# 14_TPU.net
KiCad netlist of a schematic drawn in Altium Designer
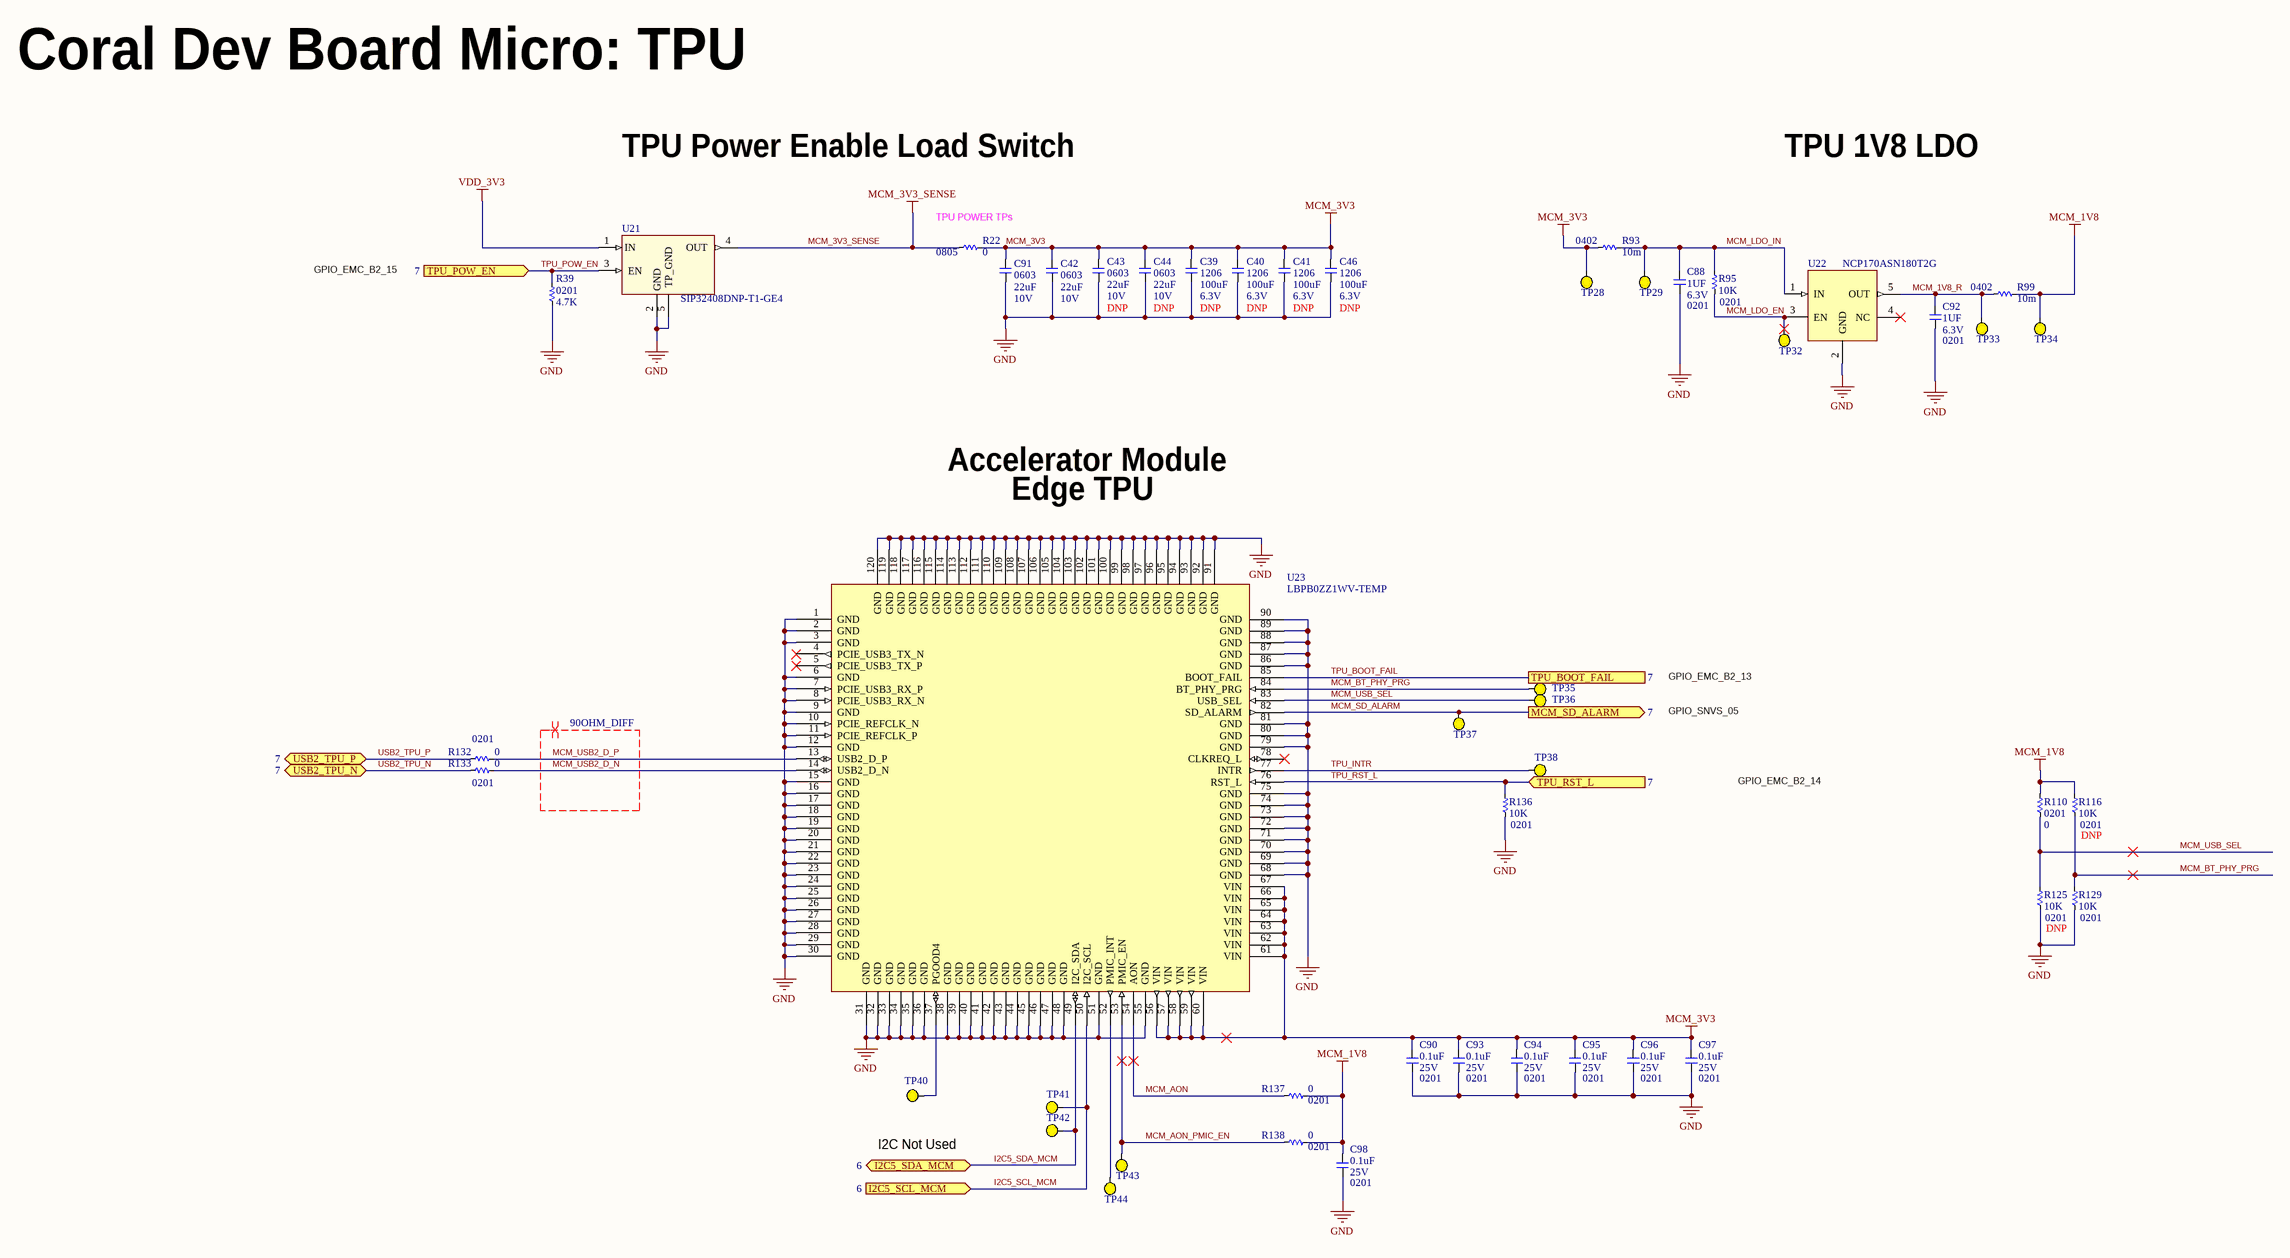
[diagram p0: 14 TPU.SchDoc]

(export (version "E")
  (design (tool "Eeschema 10.0.6"))
  (components
    (comp (ref "C39")
      (value "100uF")
      (footprint "C1206Y_1.90MM")
      (description "CAP, CER, X5R, 100UF, 6.3V, 20%, 1206")
      (fields
        (field (name "MFG") "MURATA")
        (field (name "PACKAGE") "1206")
        (field (name "VOLTAGE") "6.3V")
        (field (name "TOLERANCE") "20%")
        (field (name "DNP") "DNP")
      )
      (libsource (lib "AltiumReleaseLibDB") (part "__Template_Cap"))
    )
    (comp (ref "C40")
      (value "100uF")
      (footprint "C1206Y_1.90MM")
      (description "CAP, CER, X5R, 100UF, 6.3V, 20%, 1206")
      (fields
        (field (name "MFG") "MURATA")
        (field (name "PACKAGE") "1206")
        (field (name "VOLTAGE") "6.3V")
        (field (name "TOLERANCE") "20%")
        (field (name "DNP") "DNP")
      )
      (libsource (lib "AltiumReleaseLibDB") (part "__Template_Cap"))
    )
    (comp (ref "C41")
      (value "100uF")
      (footprint "C1206Y_1.90MM")
      (description "CAP, CER, X5R, 100UF, 6.3V, 20%, 1206")
      (fields
        (field (name "MFG") "MURATA")
        (field (name "PACKAGE") "1206")
        (field (name "VOLTAGE") "6.3V")
        (field (name "TOLERANCE") "20%")
        (field (name "DNP") "DNP")
      )
      (libsource (lib "AltiumReleaseLibDB") (part "__Template_Cap"))
    )
    (comp (ref "C42")
      (value "22uF")
      (footprint "C0603")
      (description "CAP, CER, X5R, 22uF, 20%, 10V, 0603")
      (fields
        (field (name "MFG") "TDK")
        (field (name "PACKAGE") "0603")
        (field (name "VOLTAGE") "10V")
        (field (name "TOLERANCE") "20%")
      )
      (libsource (lib "AltiumReleaseLibDB") (part "__Template_Cap"))
    )
    (comp (ref "C43")
      (value "22uF")
      (footprint "C0603")
      (description "CAP, CER, X5R, 22uF, 20%, 10V, 0603")
      (fields
        (field (name "MFG") "SAMSUNG")
        (field (name "PACKAGE") "0603")
        (field (name "VOLTAGE") "10V")
        (field (name "TOLERANCE") "20%")
        (field (name "DNP") "DNP")
      )
      (libsource (lib "AltiumReleaseLibDB") (part "__Template_Cap"))
    )
    (comp (ref "C44")
      (value "22uF")
      (footprint "C0603")
      (description "CAP, CER, X5R, 22uF, 20%, 10V, 0603")
      (fields
        (field (name "MFG") "SAMSUNG")
        (field (name "PACKAGE") "0603")
        (field (name "VOLTAGE") "10V")
        (field (name "TOLERANCE") "20%")
        (field (name "DNP") "DNP")
      )
      (libsource (lib "AltiumReleaseLibDB") (part "__Template_Cap"))
    )
    (comp (ref "C46")
      (value "100uF")
      (footprint "C1206Y_1.90MM")
      (description "CAP, CER, X5R, 100UF, 6.3V, 20%, 1206")
      (fields
        (field (name "MFG") "MURATA")
        (field (name "PACKAGE") "1206")
        (field (name "VOLTAGE") "6.3V")
        (field (name "TOLERANCE") "20%")
        (field (name "DNP") "DNP")
      )
      (libsource (lib "AltiumReleaseLibDB") (part "__Template_Cap"))
    )
    (comp (ref "C88")
      (value "1UF")
      (footprint "C0201_H0.39MM")
      (description "CAP, CER, X6S, 1uF, 20%, 6.3V, 0201, 0.39mm")
      (fields
        (field (name "MFG") "MURATA")
        (field (name "PACKAGE") "0201")
        (field (name "VOLTAGE") "6.3V")
        (field (name "TOLERANCE") "20%")
      )
      (libsource (lib "AltiumReleaseLibDB") (part "__Template_Cap"))
    )
    (comp (ref "C90")
      (value "0.1uF")
      (footprint "C0201Y")
      (description "CAP, CER, X5R, 0.1uF, 25V, 20%, 0201, 0.33mm T")
      (fields
        (field (name "MFG") "MURATA")
        (field (name "PACKAGE") "0201")
        (field (name "VOLTAGE") "25V")
        (field (name "TOLERANCE") "20%")
      )
      (libsource (lib "AltiumReleaseLibDB") (part "__Template_Cap"))
    )
    (comp (ref "C91")
      (value "22uF")
      (footprint "C0603")
      (description "CAP, CER, X5R, 22uF, 20%, 10V, 0603")
      (fields
        (field (name "MFG") "TDK")
        (field (name "PACKAGE") "0603")
        (field (name "VOLTAGE") "10V")
        (field (name "TOLERANCE") "20%")
      )
      (libsource (lib "AltiumReleaseLibDB") (part "__Template_Cap"))
    )
    (comp (ref "C92")
      (value "1UF")
      (footprint "C0201_H0.39MM")
      (description "CAP, CER, X6S, 1uF, 20%, 6.3V, 0201, 0.39mm")
      (fields
        (field (name "MFG") "MURATA")
        (field (name "PACKAGE") "0201")
        (field (name "VOLTAGE") "6.3V")
        (field (name "TOLERANCE") "20%")
      )
      (libsource (lib "AltiumReleaseLibDB") (part "__Template_Cap"))
    )
    (comp (ref "C93")
      (value "0.1uF")
      (footprint "C0201Y")
      (description "CAP, CER, X5R, 0.1uF, 25V, 20%, 0201, 0.33mm T")
      (fields
        (field (name "MFG") "MURATA")
        (field (name "PACKAGE") "0201")
        (field (name "VOLTAGE") "25V")
        (field (name "TOLERANCE") "20%")
      )
      (libsource (lib "AltiumReleaseLibDB") (part "__Template_Cap"))
    )
    (comp (ref "C94")
      (value "0.1uF")
      (footprint "C0201Y")
      (description "CAP, CER, X5R, 0.1uF, 25V, 20%, 0201, 0.33mm T")
      (fields
        (field (name "MFG") "MURATA")
        (field (name "PACKAGE") "0201")
        (field (name "VOLTAGE") "25V")
        (field (name "TOLERANCE") "20%")
      )
      (libsource (lib "AltiumReleaseLibDB") (part "__Template_Cap"))
    )
    (comp (ref "C95")
      (value "0.1uF")
      (footprint "C0201Y")
      (description "CAP, CER, X5R, 0.1uF, 25V, 20%, 0201, 0.33mm T")
      (fields
        (field (name "MFG") "MURATA")
        (field (name "PACKAGE") "0201")
        (field (name "VOLTAGE") "25V")
        (field (name "TOLERANCE") "20%")
      )
      (libsource (lib "AltiumReleaseLibDB") (part "__Template_Cap"))
    )
    (comp (ref "C96")
      (value "0.1uF")
      (footprint "C0201Y")
      (description "CAP, CER, X5R, 0.1uF, 25V, 20%, 0201, 0.33mm T")
      (fields
        (field (name "MFG") "MURATA")
        (field (name "PACKAGE") "0201")
        (field (name "VOLTAGE") "25V")
        (field (name "TOLERANCE") "20%")
      )
      (libsource (lib "AltiumReleaseLibDB") (part "__Template_Cap"))
    )
    (comp (ref "C97")
      (value "0.1uF")
      (footprint "C0201Y")
      (description "CAP, CER, X5R, 0.1uF, 25V, 20%, 0201, 0.33mm T")
      (fields
        (field (name "MFG") "MURATA")
        (field (name "PACKAGE") "0201")
        (field (name "VOLTAGE") "25V")
        (field (name "TOLERANCE") "20%")
      )
      (libsource (lib "AltiumReleaseLibDB") (part "__Template_Cap"))
    )
    (comp (ref "C98")
      (value "0.1uF")
      (footprint "C0201Y")
      (description "CAP, CER, X5R, 0.1uF, 25V, 20%, 0201, 0.33mm T")
      (fields
        (field (name "MFG") "MURATA")
        (field (name "PACKAGE") "0201")
        (field (name "VOLTAGE") "25V")
        (field (name "TOLERANCE") "20%")
      )
      (libsource (lib "AltiumReleaseLibDB") (part "__Template_Cap"))
    )
    (comp (ref "R22")
      (value "0")
      (footprint "R0805")
      (description "RES, 0, JUMPER, 1/8W, 0805")
      (fields (field (name "MFG") "YAGEO") (field (name "PACKAGE") "0805") (field (name "POWER") "1/8W"))
      (libsource (lib "AltiumReleaseLibDB") (part "__Template_Resistor"))
    )
    (comp (ref "R39")
      (value "4.7K")
      (footprint "R0201")
      (description "RES, 4.7K, 5%, 1/20W, 0201")
      (fields (field (name "MFG") "YAGEO") (field (name "PACKAGE") "0201") (field (name "POWER") "1/20W"))
      (libsource (lib "AltiumReleaseLibDB") (part "__Template_Resistor"))
    )
    (comp (ref "R93")
      (value "10m")
      (footprint "R0402")
      (description "RES, 0.01, 5%, 1/4W, 0402")
      (fields (field (name "MFG") "YAGEO") (field (name "PACKAGE") "0402") (field (name "POWER") "1/4W"))
      (libsource (lib "AltiumReleaseLibDB") (part "__Template_Resistor"))
    )
    (comp (ref "R95")
      (value "10K")
      (footprint "R0201")
      (description "RES, 10K, 1%, 1/20W, 0201")
      (fields (field (name "MFG") "YAGEO") (field (name "PACKAGE") "0201") (field (name "POWER") "1/20W"))
      (libsource (lib "AltiumReleaseLibDB") (part "__Template_Resistor"))
    )
    (comp (ref "R99")
      (value "10m")
      (footprint "R0402")
      (description "RES, 0.01, 5%, 1/4W, 0402")
      (fields (field (name "MFG") "YAGEO") (field (name "PACKAGE") "0402") (field (name "POWER") "1/4W"))
      (libsource (lib "AltiumReleaseLibDB") (part "__Template_Resistor"))
    )
    (comp (ref "R110")
      (value "0")
      (footprint "R0201")
      (description "RES, 0.0, 1/20W, 0201")
      (fields (field (name "MFG") "PANASONIC") (field (name "PACKAGE") "0201") (field (name "POWER") "1/20W"))
      (libsource (lib "AltiumReleaseLibDB") (part "__Template_Resistor"))
    )
    (comp (ref "R116")
      (value "10K")
      (footprint "R0201")
      (description "RES, 10K, 1%, 1/20W, 0201")
      (fields
        (field (name "MFG") "YAGEO")
        (field (name "PACKAGE") "0201")
        (field (name "POWER") "1/20W")
        (field (name "DNP") "DNP")
      )
      (libsource (lib "AltiumReleaseLibDB") (part "__Template_Resistor"))
    )
    (comp (ref "R125")
      (value "10K")
      (footprint "R0201")
      (description "RES, 10K, 1%, 1/20W, 0201")
      (fields
        (field (name "MFG") "YAGEO")
        (field (name "PACKAGE") "0201")
        (field (name "POWER") "1/20W")
        (field (name "DNP") "DNP")
      )
      (libsource (lib "AltiumReleaseLibDB") (part "__Template_Resistor"))
    )
    (comp (ref "R129")
      (value "10K")
      (footprint "R0201")
      (description "RES, 10K, 1%, 1/20W, 0201")
      (fields (field (name "MFG") "YAGEO") (field (name "PACKAGE") "0201") (field (name "POWER") "1/20W"))
      (libsource (lib "AltiumReleaseLibDB") (part "__Template_Resistor"))
    )
    (comp (ref "R132")
      (value "0")
      (footprint "R0201")
      (description "RES, 0.0, 1/20W, 0201")
      (fields (field (name "MFG") "PANASONIC") (field (name "PACKAGE") "0201") (field (name "POWER") "1/20W"))
      (libsource (lib "AltiumReleaseLibDB") (part "__Template_Resistor"))
    )
    (comp (ref "R133")
      (value "0")
      (footprint "R0201")
      (description "RES, 0.0, 1/20W, 0201")
      (fields (field (name "MFG") "PANASONIC") (field (name "PACKAGE") "0201") (field (name "POWER") "1/20W"))
      (libsource (lib "AltiumReleaseLibDB") (part "__Template_Resistor"))
    )
    (comp (ref "R136")
      (value "10K")
      (footprint "R0201")
      (description "RES, 10K, 1%, 1/20W, 0201")
      (fields (field (name "MFG") "YAGEO") (field (name "PACKAGE") "0201") (field (name "POWER") "1/20W"))
      (libsource (lib "AltiumReleaseLibDB") (part "__Template_Resistor"))
    )
    (comp (ref "R137")
      (value "0")
      (footprint "R0201")
      (description "RES, 0.0, 1/20W, 0201")
      (fields (field (name "MFG") "PANASONIC") (field (name "PACKAGE") "0201") (field (name "POWER") "1/20W"))
      (libsource (lib "AltiumReleaseLibDB") (part "__Template_Resistor"))
    )
    (comp (ref "R138")
      (value "0")
      (footprint "R0201")
      (description "RES, 0.0, 1/20W, 0201")
      (fields (field (name "MFG") "PANASONIC") (field (name "PACKAGE") "0201") (field (name "POWER") "1/20W"))
      (libsource (lib "AltiumReleaseLibDB") (part "__Template_Resistor"))
    )
    (comp (ref "TP28")
      (value "TESTPAD_25MIL")
      (footprint "TESTPAD_SMT_25MIL")
      (description "TESTPAD_SMT_25MIL")
      (fields (field (name "MFG") "_PCB Feature"))
      (libsource (lib "AltiumReleaseLibDB") (part "TESTPAD_25MIL"))
    )
    (comp (ref "TP29")
      (value "TESTPAD_25MIL")
      (footprint "TESTPAD_SMT_25MIL")
      (description "TESTPAD_SMT_25MIL")
      (fields (field (name "MFG") "_PCB Feature"))
      (libsource (lib "AltiumReleaseLibDB") (part "TESTPAD_25MIL"))
    )
    (comp (ref "TP32")
      (value "TESTPAD_25MIL")
      (footprint "TESTPAD_SMT_25MIL")
      (description "TESTPAD_SMT_25MIL")
      (fields (field (name "MFG") "_PCB Feature"))
      (libsource (lib "AltiumReleaseLibDB") (part "TESTPAD_25MIL"))
    )
    (comp (ref "TP33")
      (value "TESTPAD_25MIL")
      (footprint "TESTPAD_SMT_25MIL")
      (description "TESTPAD_SMT_25MIL")
      (fields (field (name "MFG") "_PCB Feature"))
      (libsource (lib "AltiumReleaseLibDB") (part "TESTPAD_25MIL"))
    )
    (comp (ref "TP34")
      (value "TESTPAD_25MIL")
      (footprint "TESTPAD_SMT_25MIL")
      (description "TESTPAD_SMT_25MIL")
      (fields (field (name "MFG") "_PCB Feature"))
      (libsource (lib "AltiumReleaseLibDB") (part "TESTPAD_25MIL"))
    )
    (comp (ref "TP35")
      (value "TESTPAD_25MIL")
      (footprint "TESTPAD_SMT_25MIL")
      (description "TESTPAD_SMT_25MIL")
      (fields (field (name "MFG") "_PCB Feature"))
      (libsource (lib "AltiumReleaseLibDB") (part "TESTPAD_25MIL"))
    )
    (comp (ref "TP36")
      (value "TESTPAD_25MIL")
      (footprint "TESTPAD_SMT_25MIL")
      (description "TESTPAD_SMT_25MIL")
      (fields (field (name "MFG") "_PCB Feature"))
      (libsource (lib "AltiumReleaseLibDB") (part "TESTPAD_25MIL"))
    )
    (comp (ref "TP37")
      (value "TESTPAD_25MIL")
      (footprint "TESTPAD_SMT_25MIL")
      (description "TESTPAD_SMT_25MIL")
      (fields (field (name "MFG") "_PCB Feature"))
      (libsource (lib "AltiumReleaseLibDB") (part "TESTPAD_25MIL"))
    )
    (comp (ref "TP38")
      (value "TESTPAD_25MIL")
      (footprint "TESTPAD_SMT_25MIL")
      (description "TESTPAD_SMT_25MIL")
      (fields (field (name "MFG") "_PCB Feature"))
      (libsource (lib "AltiumReleaseLibDB") (part "TESTPAD_25MIL"))
    )
    (comp (ref "TP40")
      (value "TESTPAD_25MIL")
      (footprint "TESTPAD_SMT_25MIL")
      (description "TESTPAD_SMT_25MIL")
      (fields (field (name "MFG") "_PCB Feature"))
      (libsource (lib "AltiumReleaseLibDB") (part "TESTPAD_25MIL"))
    )
    (comp (ref "TP41")
      (value "TESTPAD_25MIL")
      (footprint "TESTPAD_SMT_25MIL")
      (description "TESTPAD_SMT_25MIL")
      (fields (field (name "MFG") "_PCB Feature"))
      (libsource (lib "AltiumReleaseLibDB") (part "TESTPAD_25MIL"))
    )
    (comp (ref "TP42")
      (value "TESTPAD_25MIL")
      (footprint "TESTPAD_SMT_25MIL")
      (description "TESTPAD_SMT_25MIL")
      (fields (field (name "MFG") "_PCB Feature"))
      (libsource (lib "AltiumReleaseLibDB") (part "TESTPAD_25MIL"))
    )
    (comp (ref "TP43")
      (value "TESTPAD_25MIL")
      (footprint "TESTPAD_SMT_25MIL")
      (description "TESTPAD_SMT_25MIL")
      (fields (field (name "MFG") "_PCB Feature"))
      (libsource (lib "AltiumReleaseLibDB") (part "TESTPAD_25MIL"))
    )
    (comp (ref "TP44")
      (value "TESTPAD_25MIL")
      (footprint "TESTPAD_SMT_25MIL")
      (description "TESTPAD_SMT_25MIL")
      (fields (field (name "MFG") "_PCB Feature"))
      (libsource (lib "AltiumReleaseLibDB") (part "TESTPAD_25MIL"))
    )
    (comp (ref "U21")
      (value "SWITCH_SIP32408DNP-T1-GE4")
      (footprint "TDFN120X160X60-4-TP")
      (description "IC, SW, SIP32408, HIGH-SIDE, N-CH, 1:1, 1.1V TO 5.5V VCL, 3.5A, 44mOHM RDS(ON), TDFN-4")
      (fields (field (name "MFG") "Vishay Siliconix") (field (name "MFG P/N") "SIP32408DNP-T1-GE4"))
      (libsource (lib "AltiumReleaseLibDB") (part "SWITCH_SIP32408DNP-T1-GE4"))
    )
    (comp (ref "U22")
      (value "LDO_NCP170ASN180T2G")
      (footprint "TSOP95P275X110-5")
      (description "IC, REG, NCP170AS, LINEAR, FIXED, 2.2V TO 5.5V VIN, 1.8V VOUT, 150mA, TSOP-5")
      (fields (field (name "MFG") "onsemi") (field (name "MFG P/N") "NCP170ASN180T2G"))
      (libsource (lib "AltiumReleaseLibDB") (part "LDO_NCP170ASN180T2G"))
    )
    (comp (ref "U23")
      (value "LBPB0ZZ1WV-TEMP")
      (footprint "QFN120_0P5_10X15")
      (description "TPU module")
      (libsource (lib "LBPB0ZZ1WV-Valiant") (part "LBPB0ZZ1WV-TEMP"))
    )
  )
  (nets
    (net (code "1") (name "/I2C5_SCL_MCM") (class "Default")
      (node (ref "TP41") (pin "1") (pintype "passive"))
      (node (ref "U23") (pin "50") (pinfunction "I2C_SCL_50") (pintype "input"))
    )
    (net (code "2") (name "/I2C5_SDA_MCM") (class "Default")
      (node (ref "TP42") (pin "1") (pintype "passive"))
      (node (ref "U23") (pin "49") (pinfunction "I2C_SDA_49") (pintype "bidirectional"))
    )
    (net (code "3") (name "/MCM_1V8_R") (class "Default")
      (node (ref "C92") (pin "1") (pintype "passive"))
      (node (ref "R99") (pin "1") (pintype "passive"))
      (node (ref "TP33") (pin "1") (pintype "passive"))
      (node (ref "U22") (pin "5") (pinfunction "OUT_5") (pintype "output"))
    )
    (net (code "4") (name "/MCM_AON") (class "Default")
      (node (ref "R137") (pin "1") (pintype "passive"))
      (node (ref "U23") (pin "54") (pinfunction "AON_54") (pintype "power_in"))
    )
    (net (code "5") (name "/MCM_AON_PMIC_EN") (class "Default")
      (node (ref "R138") (pin "1") (pintype "passive"))
      (node (ref "TP43") (pin "1") (pintype "passive"))
      (node (ref "U23") (pin "53") (pinfunction "PMIC_EN_53") (pintype "input"))
    )
    (net (code "6") (name "/MCM_BT_PHY_PRG") (class "Default")
      (node (ref "R116") (pin "1") (pintype "passive"))
      (node (ref "R129") (pin "2") (pintype "passive"))
      (node (ref "TP35") (pin "1") (pintype "passive"))
      (node (ref "U23") (pin "84") (pinfunction "BT_PHY_PRG_84") (pintype "input"))
    )
    (net (code "7") (name "/MCM_LDO_EN") (class "Default")
      (node (ref "R95") (pin "1") (pintype "passive"))
      (node (ref "TP32") (pin "1") (pintype "passive"))
      (node (ref "U22") (pin "3") (pinfunction "EN_3") (pintype "passive"))
    )
    (net (code "8") (name "/MCM_LDO_IN") (class "Default")
      (node (ref "C88") (pin "1") (pintype "passive"))
      (node (ref "R93") (pin "2") (pintype "passive"))
      (node (ref "R95") (pin "2") (pintype "passive"))
      (node (ref "TP29") (pin "1") (pintype "passive"))
      (node (ref "U22") (pin "1") (pinfunction "IN_1") (pintype "input"))
    )
    (net (code "9") (name "/MCM_SD_ALARM") (class "Default")
      (node (ref "TP37") (pin "1") (pintype "passive"))
      (node (ref "U23") (pin "82") (pinfunction "SD_ALARM_82") (pintype "output"))
    )
    (net (code "10") (name "/MCM_USB2_D_N") (class "Default")
      (node (ref "R133") (pin "2") (pintype "passive"))
      (node (ref "U23") (pin "14") (pinfunction "USB2_D_N_14") (pintype "bidirectional"))
    )
    (net (code "11") (name "/MCM_USB2_D_P") (class "Default")
      (node (ref "R132") (pin "2") (pintype "passive"))
      (node (ref "U23") (pin "13") (pinfunction "USB2_D_P_13") (pintype "bidirectional"))
    )
    (net (code "12") (name "/MCM_USB_SEL") (class "Default")
      (node (ref "R110") (pin "1") (pintype "passive"))
      (node (ref "R125") (pin "2") (pintype "passive"))
      (node (ref "TP36") (pin "1") (pintype "passive"))
      (node (ref "U23") (pin "83") (pinfunction "USB_SEL_83") (pintype "input"))
    )
    (net (code "13") (name "/TPU_BOOT_FAIL") (class "Default")
      (node (ref "U23") (pin "85") (pinfunction "BOOT_FAIL_85") (pintype "passive"))
    )
    (net (code "14") (name "/TPU_INTR") (class "Default")
      (node (ref "TP38") (pin "1") (pintype "passive"))
      (node (ref "U23") (pin "77") (pinfunction "INTR_77") (pintype "output"))
    )
    (net (code "15") (name "/TPU_POW_EN") (class "Default")
      (node (ref "R39") (pin "2") (pintype "passive"))
      (node (ref "U21") (pin "3") (pinfunction "EN_3") (pintype "input"))
    )
    (net (code "16") (name "/TPU_RST_L") (class "Default")
      (node (ref "R136") (pin "2") (pintype "passive"))
      (node (ref "U23") (pin "76") (pinfunction "RST_L_76") (pintype "input"))
    )
    (net (code "17") (name "/USB2_TPU_N") (class "Default") (node (ref "R133") (pin "1") (pintype "passive")))
    (net (code "18") (name "/USB2_TPU_P") (class "Default") (node (ref "R132") (pin "1") (pintype "passive")))
    (net (code "19") (name "GND") (class "Default")
      (node (ref "C39") (pin "2") (pintype "passive"))
      (node (ref "C40") (pin "2") (pintype "passive"))
      (node (ref "C41") (pin "2") (pintype "passive"))
      (node (ref "C42") (pin "2") (pintype "passive"))
      (node (ref "C43") (pin "2") (pintype "passive"))
      (node (ref "C44") (pin "2") (pintype "passive"))
      (node (ref "C46") (pin "2") (pintype "passive"))
      (node (ref "C88") (pin "2") (pintype "passive"))
      (node (ref "C90") (pin "2") (pintype "passive"))
      (node (ref "C91") (pin "2") (pintype "passive"))
      (node (ref "C92") (pin "2") (pintype "passive"))
      (node (ref "C93") (pin "2") (pintype "passive"))
      (node (ref "C94") (pin "2") (pintype "passive"))
      (node (ref "C95") (pin "2") (pintype "passive"))
      (node (ref "C96") (pin "2") (pintype "passive"))
      (node (ref "C97") (pin "2") (pintype "passive"))
      (node (ref "C98") (pin "2") (pintype "passive"))
      (node (ref "R125") (pin "1") (pintype "passive"))
      (node (ref "R129") (pin "1") (pintype "passive"))
      (node (ref "R136") (pin "1") (pintype "passive"))
      (node (ref "R39") (pin "1") (pintype "passive"))
      (node (ref "U21") (pin "2") (pinfunction "GND_2") (pintype "power_in"))
      (node (ref "U21") (pin "5") (pinfunction "TP_GND_5") (pintype "power_in"))
      (node (ref "U22") (pin "2") (pinfunction "GND_2") (pintype "power_in"))
      (node (ref "U23") (pin "1") (pinfunction "GND_1") (pintype "passive"))
      (node (ref "U23") (pin "10") (pinfunction "PCIE_REFCLK_N_10") (pintype "input"))
      (node (ref "U23") (pin "100") (pinfunction "GND_100") (pintype "passive"))
      (node (ref "U23") (pin "101") (pinfunction "GND_101") (pintype "passive"))
      (node (ref "U23") (pin "102") (pinfunction "GND_102") (pintype "passive"))
      (node (ref "U23") (pin "103") (pinfunction "GND_103") (pintype "passive"))
      (node (ref "U23") (pin "104") (pinfunction "GND_104") (pintype "passive"))
      (node (ref "U23") (pin "105") (pinfunction "GND_105") (pintype "passive"))
      (node (ref "U23") (pin "106") (pinfunction "GND_106") (pintype "passive"))
      (node (ref "U23") (pin "107") (pinfunction "GND_107") (pintype "passive"))
      (node (ref "U23") (pin "108") (pinfunction "GND_108") (pintype "passive"))
      (node (ref "U23") (pin "109") (pinfunction "GND_109") (pintype "passive"))
      (node (ref "U23") (pin "11") (pinfunction "PCIE_REFCLK_P_11") (pintype "input"))
      (node (ref "U23") (pin "110") (pinfunction "GND_110") (pintype "passive"))
      (node (ref "U23") (pin "111") (pinfunction "GND_111") (pintype "passive"))
      (node (ref "U23") (pin "112") (pinfunction "GND_112") (pintype "passive"))
      (node (ref "U23") (pin "113") (pinfunction "GND_113") (pintype "passive"))
      (node (ref "U23") (pin "114") (pinfunction "GND_114") (pintype "passive"))
      (node (ref "U23") (pin "115") (pinfunction "GND_115") (pintype "passive"))
      (node (ref "U23") (pin "116") (pinfunction "GND_116") (pintype "passive"))
      (node (ref "U23") (pin "117") (pinfunction "GND_117") (pintype "passive"))
      (node (ref "U23") (pin "118") (pinfunction "GND_118") (pintype "passive"))
      (node (ref "U23") (pin "119") (pinfunction "GND_119") (pintype "passive"))
      (node (ref "U23") (pin "12") (pinfunction "GND_12") (pintype "passive"))
      (node (ref "U23") (pin "120") (pinfunction "GND_120") (pintype "passive"))
      (node (ref "U23") (pin "15") (pinfunction "GND_15") (pintype "passive"))
      (node (ref "U23") (pin "16") (pinfunction "GND_16") (pintype "passive"))
      (node (ref "U23") (pin "17") (pinfunction "GND_17") (pintype "passive"))
      (node (ref "U23") (pin "18") (pinfunction "GND_18") (pintype "passive"))
      (node (ref "U23") (pin "19") (pinfunction "GND_19") (pintype "passive"))
      (node (ref "U23") (pin "2") (pinfunction "GND_2") (pintype "passive"))
      (node (ref "U23") (pin "20") (pinfunction "GND_20") (pintype "passive"))
      (node (ref "U23") (pin "21") (pinfunction "GND_21") (pintype "passive"))
      (node (ref "U23") (pin "22") (pinfunction "GND_22") (pintype "passive"))
      (node (ref "U23") (pin "23") (pinfunction "GND_23") (pintype "passive"))
      (node (ref "U23") (pin "24") (pinfunction "GND_24") (pintype "passive"))
      (node (ref "U23") (pin "25") (pinfunction "GND_25") (pintype "passive"))
      (node (ref "U23") (pin "26") (pinfunction "GND_26") (pintype "passive"))
      (node (ref "U23") (pin "27") (pinfunction "GND_27") (pintype "passive"))
      (node (ref "U23") (pin "28") (pinfunction "GND_28") (pintype "passive"))
      (node (ref "U23") (pin "29") (pinfunction "GND_29") (pintype "passive"))
      (node (ref "U23") (pin "3") (pinfunction "GND_3") (pintype "passive"))
      (node (ref "U23") (pin "30") (pinfunction "GND_30") (pintype "passive"))
      (node (ref "U23") (pin "31") (pinfunction "GND_31") (pintype "passive"))
      (node (ref "U23") (pin "32") (pinfunction "GND_32") (pintype "passive"))
      (node (ref "U23") (pin "33") (pinfunction "GND_33") (pintype "passive"))
      (node (ref "U23") (pin "34") (pinfunction "GND_34") (pintype "passive"))
      (node (ref "U23") (pin "35") (pinfunction "GND_35") (pintype "passive"))
      (node (ref "U23") (pin "36") (pinfunction "GND_36") (pintype "passive"))
      (node (ref "U23") (pin "38") (pinfunction "GND_38") (pintype "passive"))
      (node (ref "U23") (pin "39") (pinfunction "GND_39") (pintype "passive"))
      (node (ref "U23") (pin "40") (pinfunction "GND_40") (pintype "passive"))
      (node (ref "U23") (pin "41") (pinfunction "GND_41") (pintype "passive"))
      (node (ref "U23") (pin "42") (pinfunction "GND_42") (pintype "passive"))
      (node (ref "U23") (pin "43") (pinfunction "GND_43") (pintype "passive"))
      (node (ref "U23") (pin "44") (pinfunction "GND_44") (pintype "passive"))
      (node (ref "U23") (pin "45") (pinfunction "GND_45") (pintype "passive"))
      (node (ref "U23") (pin "46") (pinfunction "GND_46") (pintype "passive"))
      (node (ref "U23") (pin "47") (pinfunction "GND_47") (pintype "passive"))
      (node (ref "U23") (pin "48") (pinfunction "GND_48") (pintype "passive"))
      (node (ref "U23") (pin "51") (pinfunction "GND_51") (pintype "passive"))
      (node (ref "U23") (pin "55") (pinfunction "GND_55") (pintype "passive"))
      (node (ref "U23") (pin "6") (pinfunction "GND_6") (pintype "passive"))
      (node (ref "U23") (pin "68") (pinfunction "GND_68") (pintype "passive"))
      (node (ref "U23") (pin "69") (pinfunction "GND_69") (pintype "passive"))
      (node (ref "U23") (pin "7") (pinfunction "PCIE_USB3_RX_P_7") (pintype "input"))
      (node (ref "U23") (pin "70") (pinfunction "GND_70") (pintype "passive"))
      (node (ref "U23") (pin "71") (pinfunction "GND_71") (pintype "passive"))
      (node (ref "U23") (pin "72") (pinfunction "GND_72") (pintype "passive"))
      (node (ref "U23") (pin "73") (pinfunction "GND_73") (pintype "passive"))
      (node (ref "U23") (pin "74") (pinfunction "GND_74") (pintype "passive"))
      (node (ref "U23") (pin "75") (pinfunction "GND_75") (pintype "passive"))
      (node (ref "U23") (pin "79") (pinfunction "GND_79") (pintype "passive"))
      (node (ref "U23") (pin "8") (pinfunction "PCIE_USB3_RX_N_8") (pintype "input"))
      (node (ref "U23") (pin "80") (pinfunction "GND_80") (pintype "passive"))
      (node (ref "U23") (pin "81") (pinfunction "GND_81") (pintype "passive"))
      (node (ref "U23") (pin "86") (pinfunction "GND_86") (pintype "passive"))
      (node (ref "U23") (pin "87") (pinfunction "GND_87") (pintype "passive"))
      (node (ref "U23") (pin "88") (pinfunction "GND_88") (pintype "passive"))
      (node (ref "U23") (pin "89") (pinfunction "GND_89") (pintype "passive"))
      (node (ref "U23") (pin "9") (pinfunction "GND_9") (pintype "passive"))
      (node (ref "U23") (pin "90") (pinfunction "GND_90") (pintype "passive"))
      (node (ref "U23") (pin "91") (pinfunction "GND_91") (pintype "passive"))
      (node (ref "U23") (pin "92") (pinfunction "GND_92") (pintype "passive"))
      (node (ref "U23") (pin "93") (pinfunction "GND_93") (pintype "passive"))
      (node (ref "U23") (pin "94") (pinfunction "GND_94") (pintype "passive"))
      (node (ref "U23") (pin "95") (pinfunction "GND_95") (pintype "passive"))
      (node (ref "U23") (pin "96") (pinfunction "GND_96") (pintype "passive"))
      (node (ref "U23") (pin "97") (pinfunction "GND_97") (pintype "passive"))
      (node (ref "U23") (pin "98") (pinfunction "GND_98") (pintype "passive"))
      (node (ref "U23") (pin "99") (pinfunction "GND_99") (pintype "passive"))
    )
    (net (code "20") (name "MCM_1V8") (class "Default")
      (node (ref "C98") (pin "1") (pintype "passive"))
      (node (ref "R110") (pin "2") (pintype "passive"))
      (node (ref "R116") (pin "2") (pintype "passive"))
      (node (ref "R137") (pin "2") (pintype "passive"))
      (node (ref "R138") (pin "2") (pintype "passive"))
      (node (ref "R99") (pin "2") (pintype "passive"))
      (node (ref "TP34") (pin "1") (pintype "passive"))
    )
    (net (code "21") (name "MCM_3V3") (class "Default")
      (node (ref "C39") (pin "1") (pintype "passive"))
      (node (ref "C40") (pin "1") (pintype "passive"))
      (node (ref "C41") (pin "1") (pintype "passive"))
      (node (ref "C42") (pin "1") (pintype "passive"))
      (node (ref "C43") (pin "1") (pintype "passive"))
      (node (ref "C44") (pin "1") (pintype "passive"))
      (node (ref "C46") (pin "1") (pintype "passive"))
      (node (ref "C90") (pin "1") (pintype "passive"))
      (node (ref "C91") (pin "1") (pintype "passive"))
      (node (ref "C93") (pin "1") (pintype "passive"))
      (node (ref "C94") (pin "1") (pintype "passive"))
      (node (ref "C95") (pin "1") (pintype "passive"))
      (node (ref "C96") (pin "1") (pintype "passive"))
      (node (ref "C97") (pin "1") (pintype "passive"))
      (node (ref "R22") (pin "2") (pintype "passive"))
      (node (ref "R93") (pin "1") (pintype "passive"))
      (node (ref "TP28") (pin "1") (pintype "passive"))
      (node (ref "U23") (pin "56") (pinfunction "VIN_56") (pintype "output"))
      (node (ref "U23") (pin "57") (pinfunction "VIN_57") (pintype "output"))
      (node (ref "U23") (pin "58") (pinfunction "VIN_58") (pintype "output"))
      (node (ref "U23") (pin "59") (pinfunction "VIN_59") (pintype "output"))
      (node (ref "U23") (pin "60") (pinfunction "VIN_60") (pintype "passive"))
      (node (ref "U23") (pin "61") (pinfunction "VIN_61") (pintype "passive"))
      (node (ref "U23") (pin "62") (pinfunction "VIN_62") (pintype "passive"))
      (node (ref "U23") (pin "63") (pinfunction "VIN_63") (pintype "passive"))
      (node (ref "U23") (pin "64") (pinfunction "VIN_64") (pintype "passive"))
      (node (ref "U23") (pin "65") (pinfunction "VIN_65") (pintype "passive"))
      (node (ref "U23") (pin "66") (pinfunction "VIN_66") (pintype "passive"))
      (node (ref "U23") (pin "67") (pinfunction "VIN_67") (pintype "passive"))
    )
    (net (code "22") (name "MCM_3V3_SENSE") (class "Default")
      (node (ref "R22") (pin "1") (pintype "passive"))
      (node (ref "U21") (pin "4") (pinfunction "OUT_4") (pintype "output"))
    )
    (net (code "23") (name "Net-(U23-PGOOD4)") (class "Default")
      (node (ref "TP40") (pin "1") (pintype "passive"))
      (node (ref "U23") (pin "37") (pinfunction "PGOOD4_37") (pintype "bidirectional"))
    )
    (net (code "24") (name "Net-(U23-PMIC_INT)") (class "Default")
      (node (ref "TP44") (pin "1") (pintype "passive"))
      (node (ref "U23") (pin "52") (pinfunction "PMIC_INT_52") (pintype "output"))
    )
    (net (code "25") (name "VDD_3V3") (class "Default")
      (node (ref "U21") (pin "1") (pinfunction "IN_1") (pintype "input"))
    )
    (net (code "26") (name "unconnected-(U22-NC-Pad4)") (class "Default")
      (node (ref "U22") (pin "4") (pinfunction "NC_4") (pintype "passive+no_connect"))
    )
    (net (code "27") (name "unconnected-(U23-CLKREQ_L-Pad78)") (class "Default")
      (node (ref "U23") (pin "78") (pinfunction "CLKREQ_L_78") (pintype "bidirectional+no_connect"))
    )
    (net (code "28") (name "unconnected-(U23-PCIE_USB3_TX_N-Pad4)") (class "Default")
      (node (ref "U23") (pin "4") (pinfunction "PCIE_USB3_TX_N_4") (pintype "output+no_connect"))
    )
    (net (code "29") (name "unconnected-(U23-PCIE_USB3_TX_P-Pad5)") (class "Default")
      (node (ref "U23") (pin "5") (pinfunction "PCIE_USB3_TX_P_5") (pintype "output+no_connect"))
    )
  )
)
